# 10_Misc.net
KiCad netlist of a schematic drawn in Altium Designer
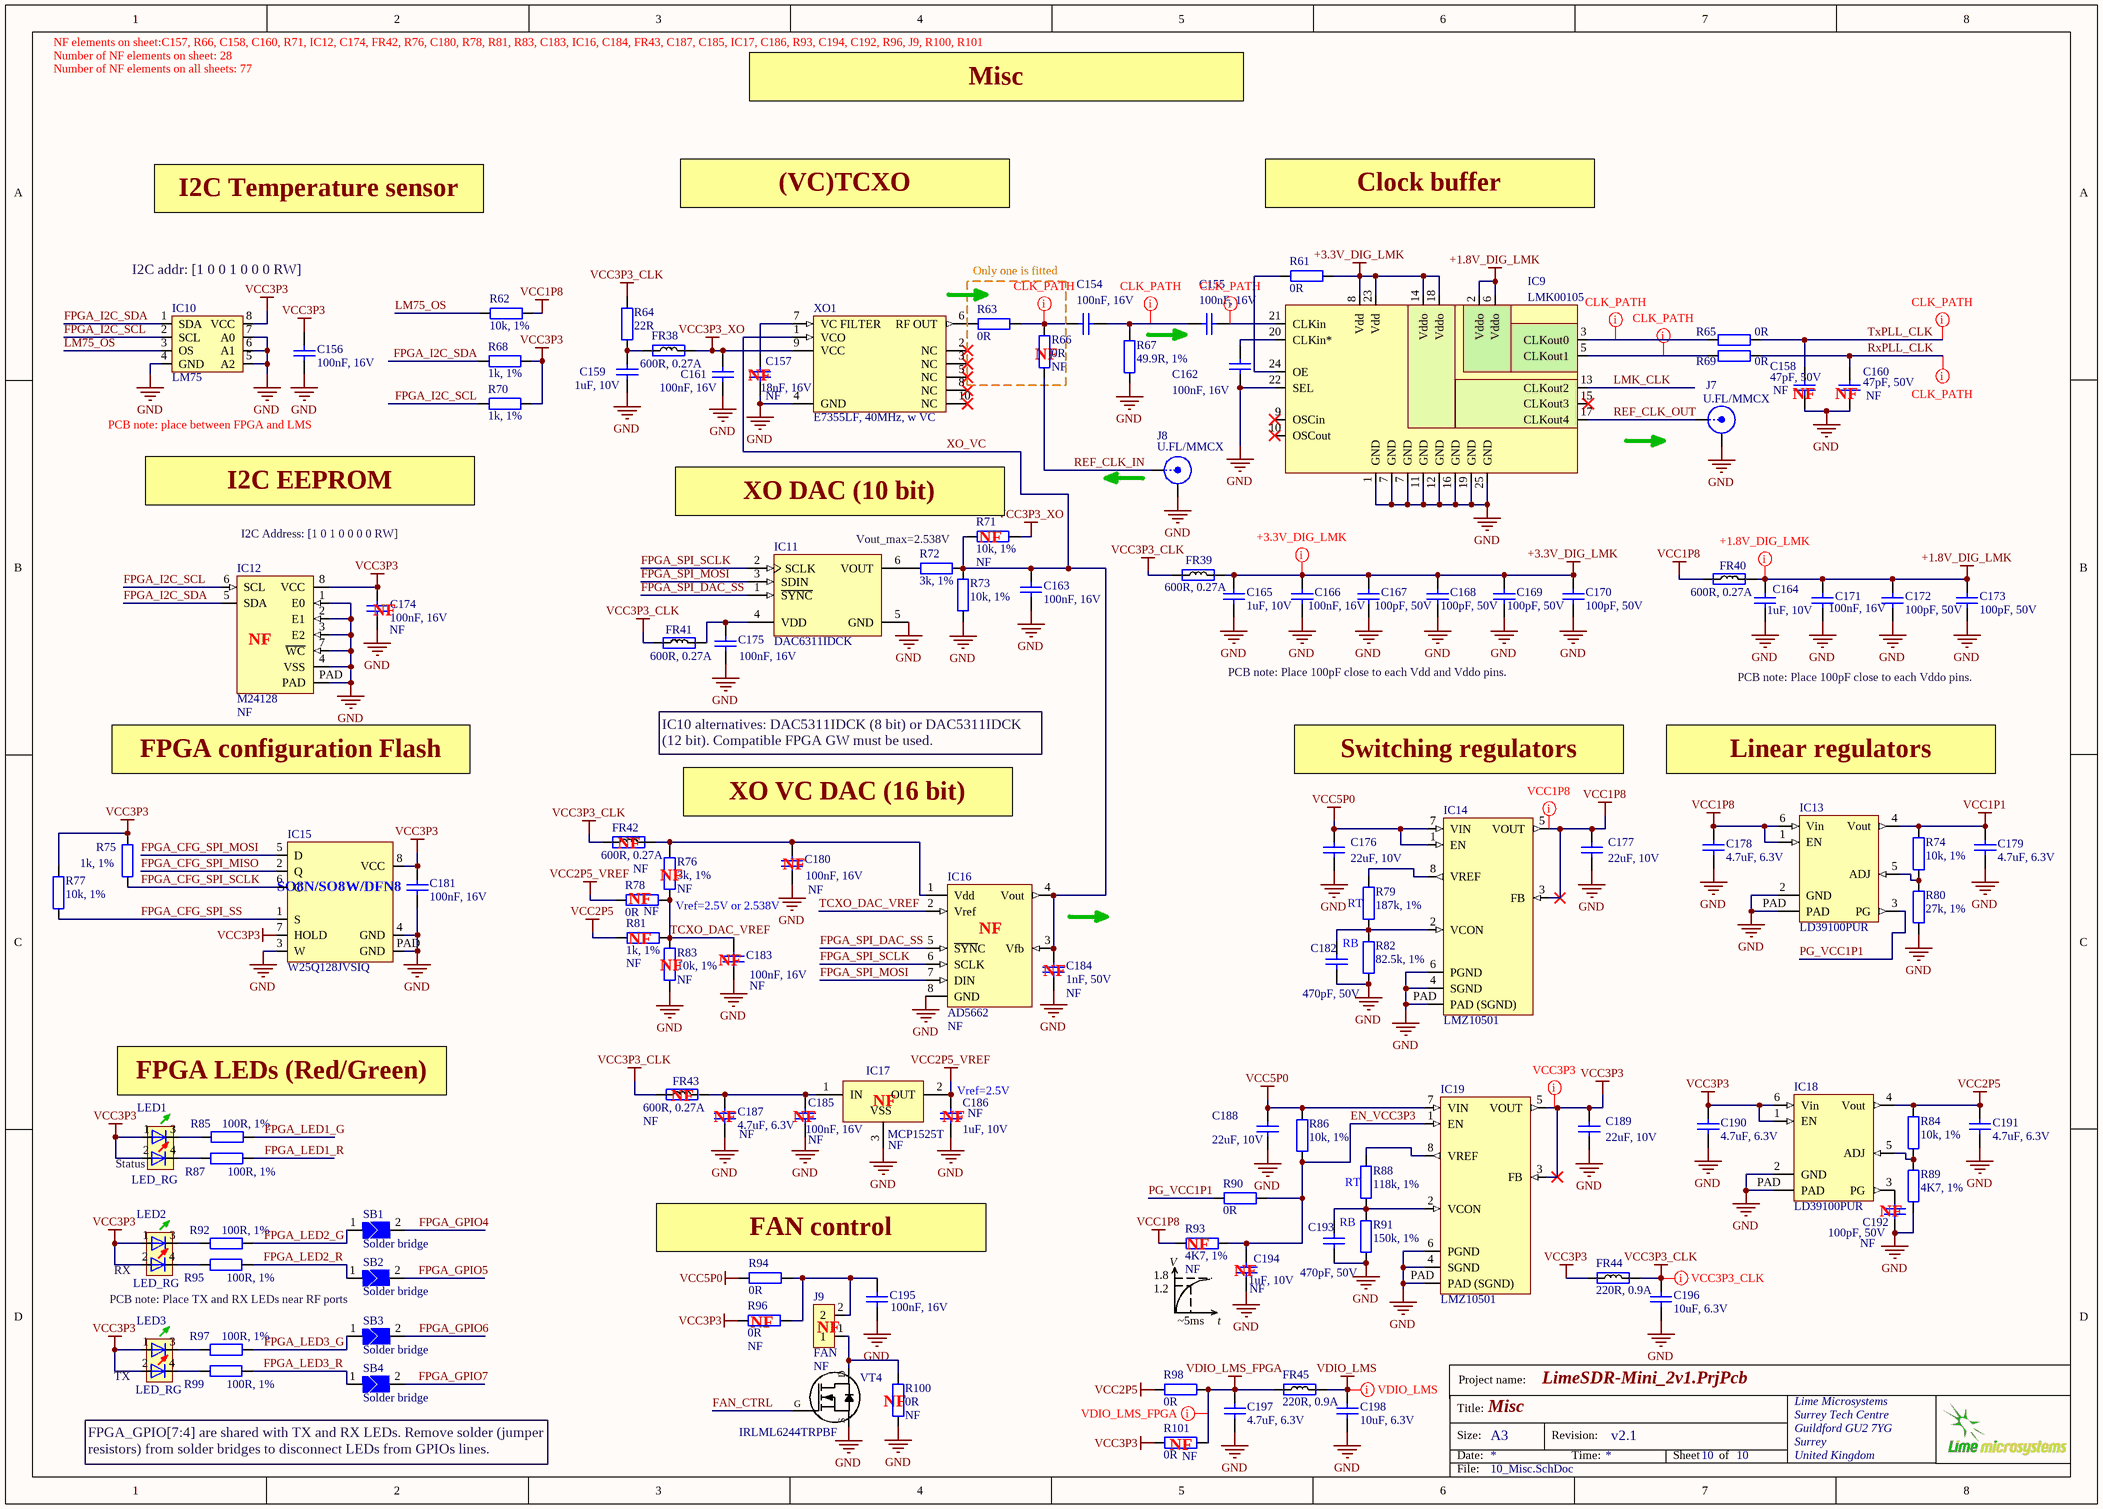
[diagram p0: 10_Misc.SchDoc]

(export (version "E")
  (design (tool "Eeschema 10.0.6"))
  (components
    (comp (ref "C154")
      (value "100nF, 16V")
      (footprint "CAP0402")
      (fields
        (field (name "MANUFACTURER") "Murata Electronics")
        (field (name "TOLERANCE") "10 %")
        (field (name "MANUFACTURER PART NUMBER") "GRM155R71C104KA88D")
      )
      (libsource (lib "LimeMicroAltiumLib_schLib") (part "Cap_0402"))
    )
    (comp (ref "C155")
      (value "100nF, 16V")
      (footprint "CAP0402")
      (fields
        (field (name "MANUFACTURER") "Murata Electronics")
        (field (name "TOLERANCE") "10 %")
        (field (name "MANUFACTURER PART NUMBER") "GRM155R71C104KA88D")
      )
      (libsource (lib "LimeMicroAltiumLib_schLib") (part "Cap_0402"))
    )
    (comp (ref "C156")
      (value "100nF, 16V")
      (footprint "CAP0402")
      (fields
        (field (name "TOLERANCE") "10 %")
        (field (name "MANUFACTURER") "Murata Electronics")
        (field (name "MANUFACTURER PART NUMBER") "GRM155R71C104KA88D")
      )
      (libsource (lib "") (part "Cap_0603_1"))
    )
    (comp (ref "C157")
      (value "18nF, 16V")
      (footprint "CAP0402")
      (fields
        (field (name "ASSEMBLY INFO") "NF")
        (field (name "MANUFACTURER") "Yageo")
        (field (name "TOLERANCE") "±10%")
      )
      (libsource (lib "LimeMicroAltiumLib_schLib") (part "Cap_0402"))
    )
    (comp (ref "C158")
      (value "47pF, 50V")
      (footprint "CAP0402")
      (fields
        (field (name "TOLERANCE") "±1%")
        (field (name "MANUFACTURER") "TDK Corporation")
        (field (name "ASSEMBLY INFO") "NF")
      )
      (libsource (lib "LimeMicroAltiumLib_schLib") (part "Cap_0402"))
    )
    (comp (ref "C159")
      (value "1uF, 10V")
      (footprint "CAP0402")
      (fields (field (name "MANUFACTURER") "TDK"))
      (libsource (lib "LimeMicroAltiumLib_schLib") (part "Cap_0402"))
    )
    (comp (ref "C160")
      (value "47pF, 50V")
      (footprint "CAP0402")
      (fields
        (field (name "TOLERANCE") "±1%")
        (field (name "MANUFACTURER") "TDK Corporation")
        (field (name "ASSEMBLY INFO") "NF")
      )
      (libsource (lib "LimeMicroAltiumLib_schLib") (part "Cap_0402"))
    )
    (comp (ref "C161")
      (value "100nF, 16V")
      (footprint "CAP0402")
      (fields
        (field (name "MANUFACTURER") "Murata Electronics")
        (field (name "TOLERANCE") "10 %")
        (field (name "MANUFACTURER PART NUMBER") "GRM155R71C104KA88D")
      )
      (libsource (lib "LimeMicroAltiumLib_schLib") (part "Cap_0402"))
    )
    (comp (ref "C162")
      (value "100nF, 16V")
      (footprint "CAP0402")
      (fields
        (field (name "MANUFACTURER") "Murata Electronics")
        (field (name "TOLERANCE") "10 %")
        (field (name "MANUFACTURER PART NUMBER") "GRM155R71C104KA88D")
      )
      (libsource (lib "LimeMicroAltiumLib_schLib") (part "Cap_0402"))
    )
    (comp (ref "C163")
      (value "100nF, 16V")
      (footprint "CAP0402")
      (fields
        (field (name "MANUFACTURER") "Murata Electronics")
        (field (name "TOLERANCE") "10 %")
        (field (name "MANUFACTURER PART NUMBER") "GRM155R71C104KA88D")
      )
      (libsource (lib "LimeMicroAltiumLib_schLib") (part "Cap_0402"))
    )
    (comp (ref "C164")
      (value "1uF, 10V")
      (footprint "CAP0402")
      (fields (field (name "MANUFACTURER") "TDK"))
      (libsource (lib "LimeMicroAltiumLib_schLib") (part "Cap_0402"))
    )
    (comp (ref "C165")
      (value "1uF, 10V")
      (footprint "CAP0402")
      (fields (field (name "MANUFACTURER") "TDK"))
      (libsource (lib "LimeMicroAltiumLib_schLib") (part "Cap_0402"))
    )
    (comp (ref "C166")
      (value "100nF, 16V")
      (footprint "CAP0402")
      (fields
        (field (name "MANUFACTURER") "Murata Electronics")
        (field (name "TOLERANCE") "10 %")
        (field (name "MANUFACTURER PART NUMBER") "GRM155R71C104KA88D")
      )
      (libsource (lib "LimeMicroAltiumLib_schLib") (part "Cap_0402"))
    )
    (comp (ref "C167")
      (value "100pF, 50V")
      (footprint "CAP0402")
      (fields (field (name "MANUFACTURER") "Yageo") (field (name "TOLERANCE") "±5%"))
      (libsource (lib "LimeMicroAltiumLib_schLib") (part "Cap_0402"))
    )
    (comp (ref "C168")
      (value "100pF, 50V")
      (footprint "CAP0402")
      (fields (field (name "MANUFACTURER") "Yageo") (field (name "TOLERANCE") "±5%"))
      (libsource (lib "LimeMicroAltiumLib_schLib") (part "Cap_0402"))
    )
    (comp (ref "C169")
      (value "100pF, 50V")
      (footprint "CAP0402")
      (fields (field (name "MANUFACTURER") "Yageo") (field (name "TOLERANCE") "±5%"))
      (libsource (lib "LimeMicroAltiumLib_schLib") (part "Cap_0402"))
    )
    (comp (ref "C170")
      (value "100pF, 50V")
      (footprint "CAP0402")
      (fields (field (name "MANUFACTURER") "Yageo") (field (name "TOLERANCE") "±5%"))
      (libsource (lib "LimeMicroAltiumLib_schLib") (part "Cap_0402"))
    )
    (comp (ref "C171")
      (value "100nF, 16V")
      (footprint "CAP0402")
      (fields
        (field (name "MANUFACTURER") "Murata Electronics")
        (field (name "TOLERANCE") "10 %")
        (field (name "MANUFACTURER PART NUMBER") "GRM155R71C104KA88D")
      )
      (libsource (lib "LimeMicroAltiumLib_schLib") (part "Cap_0402"))
    )
    (comp (ref "C172")
      (value "100pF, 50V")
      (footprint "CAP0402")
      (fields (field (name "MANUFACTURER") "Yageo") (field (name "TOLERANCE") "±5%"))
      (libsource (lib "LimeMicroAltiumLib_schLib") (part "Cap_0402"))
    )
    (comp (ref "C173")
      (value "100pF, 50V")
      (footprint "CAP0402")
      (fields (field (name "MANUFACTURER") "Yageo") (field (name "TOLERANCE") "±5%"))
      (libsource (lib "LimeMicroAltiumLib_schLib") (part "Cap_0402"))
    )
    (comp (ref "C174")
      (value "100nF, 16V")
      (footprint "CAP0402")
      (fields
        (field (name "TOLERANCE") "10 %")
        (field (name "MANUFACTURER") "Murata Electronics")
        (field (name "MANUFACTURER PART NUMBER") "GRM155R71C104KA88D")
        (field (name "ASSEMBLY INFO") "NF")
      )
      (libsource (lib "") (part "Cap_0603_1"))
    )
    (comp (ref "C175")
      (value "100nF, 16V")
      (footprint "CAP0402")
      (fields
        (field (name "TOLERANCE") "10 %")
        (field (name "MANUFACTURER") "Murata Electronics")
        (field (name "MANUFACTURER PART NUMBER") "GRM155R71C104KA88D")
      )
      (libsource (lib "") (part "Cap_0603_1"))
    )
    (comp (ref "C176")
      (value "22uF, 10V")
      (footprint "CAP0603")
      (fields (field (name "TOLERANCE") "20 %") (field (name "MANUFACTURER") "TDK Corporation"))
      (libsource (lib "") (part "Cap_0603_1"))
    )
    (comp (ref "C177")
      (value "22uF, 10V")
      (footprint "CAP0603")
      (fields (field (name "TOLERANCE") "20 %") (field (name "MANUFACTURER") "TDK Corporation"))
      (libsource (lib "") (part "Cap_0603_1"))
    )
    (comp (ref "C178")
      (value "4.7uF, 6.3V")
      (footprint "CAP0402")
      (fields
        (field (name "MANUFACTURER") "Murata Electronics North America")
        (field (name "TOLERANCE") "±20%")
      )
      (libsource (lib "LimeMicroAltiumLib_schLib") (part "Cap_0402"))
    )
    (comp (ref "C179")
      (value "4.7uF, 6.3V")
      (footprint "CAP0402")
      (fields
        (field (name "MANUFACTURER") "Murata Electronics North America")
        (field (name "TOLERANCE") "±20%")
      )
      (libsource (lib "LimeMicroAltiumLib_schLib") (part "Cap_0402"))
    )
    (comp (ref "C180")
      (value "100nF, 16V")
      (footprint "CAP0402")
      (fields
        (field (name "TOLERANCE") "10 %")
        (field (name "MANUFACTURER") "Murata Electronics")
        (field (name "MANUFACTURER PART NUMBER") "GRM155R71C104KA88D")
        (field (name "ASSEMBLY INFO") "NF")
      )
      (libsource (lib "") (part "Cap_0603_1"))
    )
    (comp (ref "C181")
      (value "100nF, 16V")
      (footprint "CAP0402")
      (fields
        (field (name "TOLERANCE") "10 %")
        (field (name "MANUFACTURER") "Murata Electronics")
        (field (name "MANUFACTURER PART NUMBER") "GRM155R71C104KA88D")
      )
      (libsource (lib "") (part "Cap_0603_1"))
    )
    (comp (ref "C182")
      (value "470pF, 50V")
      (footprint "CAP0402")
      (fields (field (name "TOLERANCE") "±5%") (field (name "MANUFACTURER") "TDK Corporation"))
      (libsource (lib "LimeMicroAltiumLib_schLib") (part "Cap_0402"))
    )
    (comp (ref "C183")
      (value "100nF, 16V")
      (footprint "CAP0402")
      (fields
        (field (name "TOLERANCE") "10 %")
        (field (name "MANUFACTURER") "Murata Electronics")
        (field (name "ASSEMBLY INFO") "NF")
      )
      (libsource (lib "LimeFPGAboard_schLib") (part "Cap_0603"))
    )
    (comp (ref "C184")
      (value "1nF, 50V")
      (footprint "CAP0402")
      (fields
        (field (name "ASSEMBLY INFO") "NF")
        (field (name "TOLERANCE") "10 %")
        (field (name "MANUFACTURER") "Murata Electronics")
      )
      (libsource (lib "") (part "Cap_0402_1"))
    )
    (comp (ref "C185")
      (value "100nF, 16V")
      (footprint "CAP0402")
      (fields
        (field (name "TOLERANCE") "10 %")
        (field (name "MANUFACTURER") "Murata Electronics")
        (field (name "ASSEMBLY INFO") "NF")
      )
      (libsource (lib "LimeFPGAboard_schLib") (part "Cap_0603"))
    )
    (comp (ref "C186")
      (value "1uF, 10V")
      (footprint "CAP0402")
      (fields (field (name "ASSEMBLY INFO") "NF") (field (name "MANUFACTURER") "TDK"))
      (libsource (lib "LimeMicroAltiumLib_schLib") (part "Cap_0402"))
    )
    (comp (ref "C187")
      (value "4.7uF, 6.3V")
      (footprint "CAP0402")
      (fields
        (field (name "ASSEMBLY INFO") "NF")
        (field (name "MANUFACTURER") "Murata Electronics North America")
        (field (name "TOLERANCE") "±20%")
      )
      (libsource (lib "LimeMicroAltiumLib_schLib") (part "Cap_0402"))
    )
    (comp (ref "C188")
      (value "22uF, 10V")
      (footprint "CAP0603")
      (fields (field (name "TOLERANCE") "20 %") (field (name "MANUFACTURER") "TDK Corporation"))
      (libsource (lib "") (part "Cap_0603_1"))
    )
    (comp (ref "C189")
      (value "22uF, 10V")
      (footprint "CAP0603")
      (fields (field (name "TOLERANCE") "20 %") (field (name "MANUFACTURER") "TDK Corporation"))
      (libsource (lib "") (part "Cap_0603_1"))
    )
    (comp (ref "C190")
      (value "4.7uF, 6.3V")
      (footprint "CAP0402")
      (fields
        (field (name "MANUFACTURER") "Murata Electronics North America")
        (field (name "TOLERANCE") "±20%")
      )
      (libsource (lib "LimeMicroAltiumLib_schLib") (part "Cap_0402"))
    )
    (comp (ref "C191")
      (value "4.7uF, 6.3V")
      (footprint "CAP0402")
      (fields
        (field (name "MANUFACTURER") "Murata Electronics North America")
        (field (name "TOLERANCE") "±20%")
      )
      (libsource (lib "LimeMicroAltiumLib_schLib") (part "Cap_0402"))
    )
    (comp (ref "C192")
      (value "100pF, 50V")
      (footprint "CAP0402")
      (fields
        (field (name "ASSEMBLY INFO") "NF")
        (field (name "MANUFACTURER") "Yageo")
        (field (name "TOLERANCE") "±5%")
      )
      (libsource (lib "LimeMicroAltiumLib_schLib") (part "Cap_0402"))
    )
    (comp (ref "C193")
      (value "470pF, 50V")
      (footprint "CAP0402")
      (fields (field (name "TOLERANCE") "±5%") (field (name "MANUFACTURER") "TDK Corporation"))
      (libsource (lib "LimeMicroAltiumLib_schLib") (part "Cap_0402"))
    )
    (comp (ref "C194")
      (value "1uF, 10V")
      (footprint "CAP0402")
      (fields (field (name "ASSEMBLY INFO") "NF") (field (name "MANUFACTURER") "TDK"))
      (libsource (lib "LimeMicroAltiumLib_schLib") (part "Cap_0402"))
    )
    (comp (ref "C195")
      (value "100nF, 16V")
      (footprint "CAP0402")
      (fields
        (field (name "TOLERANCE") "10 %")
        (field (name "MANUFACTURER") "Murata Electronics")
        (field (name "MANUFACTURER PART NUMBER") "GRM155R71C104KA88D")
      )
      (libsource (lib "") (part "Cap_0603_1"))
    )
    (comp (ref "C196")
      (value "10uF, 6.3V")
      (footprint "CAP0603")
      (fields (field (name "TOLERANCE") "±20%") (field (name "MANUFACTURER") "Yageo"))
      (libsource (lib "") (part "Cap_0603_1"))
    )
    (comp (ref "C197")
      (value "4.7uF, 6.3V")
      (footprint "CAP0402")
      (fields
        (field (name "MANUFACTURER") "Murata Electronics North America")
        (field (name "TOLERANCE") "±20%")
      )
      (libsource (lib "LimeMicroAltiumLib_schLib") (part "Cap_0402"))
    )
    (comp (ref "C198")
      (value "10uF, 6.3V")
      (footprint "CAP0603")
      (fields (field (name "TOLERANCE") "±20%") (field (name "MANUFACTURER") "Yageo"))
      (libsource (lib "") (part "Cap_0603_1"))
    )
    (comp (ref "FR38")
      (value "600R, 0.27A")
      (footprint "RES0201")
      (fields (field (name "MANUFACTURER") "Taiyo Yuden"))
      (libsource (lib "LimeMicroAltiumLib_schLib") (part "Ferrite"))
    )
    (comp (ref "FR39")
      (value "600R, 0.27A")
      (footprint "RES0201")
      (fields (field (name "MANUFACTURER") "Taiyo Yuden"))
      (libsource (lib "LimeMicroAltiumLib_schLib") (part "Ferrite"))
    )
    (comp (ref "FR40")
      (value "600R, 0.27A")
      (footprint "RES0201")
      (fields (field (name "MANUFACTURER") "Taiyo Yuden"))
      (libsource (lib "LimeMicroAltiumLib_schLib") (part "Ferrite"))
    )
    (comp (ref "FR41")
      (value "600R, 0.27A")
      (footprint "RES0201")
      (fields (field (name "MANUFACTURER") "Taiyo Yuden"))
      (libsource (lib "LimeMicroAltiumLib_schLib") (part "Ferrite"))
    )
    (comp (ref "FR42")
      (value "600R, 0.27A")
      (footprint "RES0201")
      (fields (field (name "MANUFACTURER") "Taiyo Yuden") (field (name "ASSEMBLY INFO") "NF"))
      (libsource (lib "LimeMicroAltiumLib_schLib") (part "Ferrite"))
    )
    (comp (ref "FR43")
      (value "600R, 0.27A")
      (footprint "RES0201")
      (fields (field (name "MANUFACTURER") "Taiyo Yuden") (field (name "ASSEMBLY INFO") "NF"))
      (libsource (lib "LimeMicroAltiumLib_schLib") (part "Ferrite"))
    )
    (comp (ref "FR44")
      (value "220R, 0.9A")
      (footprint "RES0402")
      (fields (field (name "MANUFACTURER") "TDK Corporation"))
      (libsource (lib "LimeFPGAboard_schLib") (part "Ferrite"))
    )
    (comp (ref "FR45")
      (value "220R, 0.9A")
      (footprint "RES0402")
      (fields (field (name "MANUFACTURER") "TDK Corporation"))
      (libsource (lib "LimeFPGAboard_schLib") (part "Ferrite"))
    )
    (comp (ref "IC9")
      (value "LMK00105")
      (footprint "LMK00105SQ")
      (fields (field (name "MANUFACTURER") "Texas Instruments"))
      (libsource (lib "LimeMicroAltiumLib_schLib") (part "LMK00105"))
    )
    (comp (ref "IC10")
      (value "LM75")
      (footprint "HWSON8_LM75")
      (fields (field (name "MANUFACTURER") "NXP Semiconductors"))
      (libsource (lib "LimeMicroAltiumLib_schLib") (part "LM75"))
    )
    (comp (ref "IC11")
      (value "DAC6311IDCK")
      (footprint "AD5601_SOT23-6")
      (fields (field (name "MANUFACTURER") "Texas Instruments"))
      (libsource (lib "LimeMicroAltiumLib_schLib") (part "AD5601BKSZ-REEL7"))
    )
    (comp (ref "IC12")
      (value "M24128")
      (footprint "M24128-DFMC6TG")
      (fields (field (name "MANUFACTURER") "STMicroelectronics") (field (name "ASSEMBLY INFO") "NF"))
      (libsource (lib "LimeMicroAltiumLib_schLib") (part "M24128-DFMC6TG"))
    )
    (comp (ref "IC13")
      (value "LD39100PUR")
      (footprint "LD39100PUR")
      (fields (field (name "MANUFACTURER") "STMicroelectronics"))
      (libsource (lib "LimeMicroAltiumLib_schLib") (part "LD39100PUR"))
    )
    (comp (ref "IC14")
      (value "LMZ10501")
      (footprint "LMZ10501")
      (fields (field (name "MANUFACTURER") "Texas Instruments"))
      (libsource (lib "LimeMicroAltiumLib_schLib") (part "LMZ10501"))
    )
    (comp (ref "IC15")
      (value "W25Q128JVSIQ")
      (footprint "S25FL164K_WSON8_DFN6")
      (fields (field (name "MANUFACTURER") "Winbond"))
      (libsource (lib "LimeMicroAltiumLib_schLib_r03") (part "M25P40_with_pad"))
    )
    (comp (ref "IC16")
      (value "AD5662")
      (footprint "AD5662_SOT23-8")
      (fields (field (name "MANUFACTURER") "Analog Devices Inc.") (field (name "ASSEMBLY INFO") "NF"))
      (libsource (lib "LimeMicroAltiumLib_schLib") (part "AD5662"))
    )
    (comp (ref "IC17")
      (value "MCP1525T")
      (footprint "SOT23-3_v2")
      (description "2.5V Voltage Reference, 3-Pin SOT-23, Industrial Temperature, Tape and Reel")
      (fields
        (field (name "MANUFACTURER") "Microchip Technology")
        (field (name "TOLERANCE") "±1%")
        (field (name "ASSEMBLY INFO") "NF")
      )
      (libsource (lib "LimeMicroAltiumLib_schLib") (part "MCP1525T-I/TT"))
    )
    (comp (ref "IC18")
      (value "LD39100PUR")
      (footprint "LD39100PUR")
      (fields (field (name "MANUFACTURER") "STMicroelectronics"))
      (libsource (lib "LimeMicroAltiumLib_schLib") (part "LD39100PUR"))
    )
    (comp (ref "IC19")
      (value "LMZ10501")
      (footprint "LMZ10501")
      (fields (field (name "MANUFACTURER") "Texas Instruments"))
      (libsource (lib "LimeMicroAltiumLib_schLib") (part "LMZ10501"))
    )
    (comp (ref "J7")
      (value "U.FL/MMCX")
      (footprint "MMCX_UFL_conn_u")
      (description "CONN UMC RCPT STR 50 OHM SMD")
      (fields (field (name "MANUFACTURER") "Molex, LLC"))
      (libsource (lib "LimeMicroAltiumLib_schLib") (part "RF_IF_connector"))
    )
    (comp (ref "J8")
      (value "U.FL/MMCX")
      (footprint "MMCX_UFL_conn_u")
      (description "CONN UMC RCPT STR 50 OHM SMD")
      (fields (field (name "MANUFACTURER") "Molex, LLC"))
      (libsource (lib "LimeMicroAltiumLib_schLib") (part "RF_IF_connector"))
    )
    (comp (ref "J9")
      (value "FAN")
      (footprint "Header2x1_TH_v2")
      (fields (field (name "ASSEMBLY INFO") "NF") (field (name "MANUFACTURER") "3M"))
      (libsource (lib "LimeFPGAboard_schLib") (part "Jumper"))
    )
    (comp (ref "LED1")
      (value "LED_RG")
      (footprint "LED-2x0603")
      (fields (field (name "MANUFACTURER") "Avago Technologies US Inc."))
      (libsource (lib "LimeMicroAltiumLib_schLib") (part "LED_green_red_SMD"))
    )
    (comp (ref "LED2")
      (value "LED_RG")
      (footprint "LED-2x0603")
      (fields (field (name "MANUFACTURER") "Avago Technologies US Inc."))
      (libsource (lib "LimeMicroAltiumLib_schLib") (part "LED_green_red_SMD"))
    )
    (comp (ref "LED3")
      (value "LED_RG")
      (footprint "LED-2x0603")
      (fields (field (name "MANUFACTURER") "Avago Technologies US Inc."))
      (libsource (lib "LimeMicroAltiumLib_schLib") (part "LED_green_red_SMD"))
    )
    (comp (ref "R61")
      (value "0R")
      (footprint "RES0402")
      (fields (field (name "MANUFACTURER") "Yageo") (field (name "TOLERANCE") "Jumper"))
      (libsource (lib "LimeMicroAltiumLib_schLib") (part "Res_0402"))
    )
    (comp (ref "R62")
      (value "10k, 1%")
      (footprint "RES0402")
      (fields (field (name "MANUFACTURER") "Yageo") (field (name "TOLERANCE") "±1%"))
      (libsource (lib "LimeMicroAltiumLib_schLib") (part "Res_0402"))
    )
    (comp (ref "R63")
      (value "0R")
      (footprint "RES0402")
      (fields (field (name "MANUFACTURER") "Yageo") (field (name "TOLERANCE") "Jumper"))
      (libsource (lib "LimeMicroAltiumLib_schLib") (part "Res_0402"))
    )
    (comp (ref "R64")
      (value "22R")
      (footprint "RES0402")
      (fields (field (name "TOLERANCE") "±1%") (field (name "MANUFACTURER") "Yageo"))
      (libsource (lib "LimeFPGAboard_schLib") (part "Res_0402"))
    )
    (comp (ref "R65")
      (value "0R")
      (footprint "RES0402")
      (fields (field (name "MANUFACTURER") "Yageo") (field (name "TOLERANCE") "Jumper"))
      (libsource (lib "LimeFPGAboard_schLib") (part "Res_0402"))
    )
    (comp (ref "R66")
      (value "0R")
      (footprint "RES0402")
      (fields
        (field (name "ASSEMBLY INFO") "NF")
        (field (name "MANUFACTURER") "Yageo")
        (field (name "TOLERANCE") "Jumper")
      )
      (libsource (lib "LimeMicroAltiumLib_schLib") (part "Res_0402"))
    )
    (comp (ref "R67")
      (value "49.9R, 1%")
      (footprint "RES0402")
      (fields
        (field (name "TOLERANCE") "±1%")
        (field (name "MANUFACTURER") "Samsung Electro-Mechanics America, Inc.")
      )
      (libsource (lib "LimeMicroAltiumLib_schLib") (part "Res_0402"))
    )
    (comp (ref "R68")
      (value "1k, 1%")
      (footprint "RES0402")
      (fields (field (name "MANUFACTURER") "Stackpole Electronics Inc") (field (name "TOLERANCE") "±1%"))
      (libsource (lib "LimeMicroAltiumLib_schLib") (part "Res_0402"))
    )
    (comp (ref "R69")
      (value "0R")
      (footprint "RES0402")
      (fields (field (name "MANUFACTURER") "Yageo") (field (name "TOLERANCE") "Jumper"))
      (libsource (lib "LimeFPGAboard_schLib") (part "Res_0402"))
    )
    (comp (ref "R70")
      (value "1k, 1%")
      (footprint "RES0402")
      (fields (field (name "MANUFACTURER") "Stackpole Electronics Inc") (field (name "TOLERANCE") "±1%"))
      (libsource (lib "LimeMicroAltiumLib_schLib") (part "Res_0402"))
    )
    (comp (ref "R71")
      (value "10k, 1%")
      (footprint "RES0402")
      (fields
        (field (name "ASSEMBLY INFO") "NF")
        (field (name "MANUFACTURER") "Yageo")
        (field (name "TOLERANCE") "±1%")
      )
      (libsource (lib "LimeMicroAltiumLib_schLib") (part "Res_0402"))
    )
    (comp (ref "R72")
      (value "3k, 1%")
      (footprint "RES0402")
      (fields (field (name "TOLERANCE") "±1%") (field (name "MANUFACTURER") "Vishay Dale"))
      (libsource (lib "LimeMicroAltiumLib_schLib") (part "Res_0402"))
    )
    (comp (ref "R73")
      (value "10k, 1%")
      (footprint "RES0402")
      (fields (field (name "MANUFACTURER") "Yageo") (field (name "TOLERANCE") "±1%"))
      (libsource (lib "LimeMicroAltiumLib_schLib") (part "Res_0402"))
    )
    (comp (ref "R74")
      (value "10k, 1%")
      (footprint "RES0402")
      (fields (field (name "MANUFACTURER") "Yageo") (field (name "TOLERANCE") "±1%"))
      (libsource (lib "LimeMicroAltiumLib_schLib") (part "Res_0402"))
    )
    (comp (ref "R75")
      (value "1k, 1%")
      (footprint "RES0402")
      (fields (field (name "MANUFACTURER") "Stackpole Electronics Inc") (field (name "TOLERANCE") "±1%"))
      (libsource (lib "LimeMicroAltiumLib_schLib") (part "Res_0402"))
    )
    (comp (ref "R76")
      (value "3k, 1%")
      (footprint "RES0402")
      (fields
        (field (name "ASSEMBLY INFO") "NF")
        (field (name "TOLERANCE") "±1%")
        (field (name "MANUFACTURER") "Vishay Dale")
      )
      (libsource (lib "") (part "Res_0402_1"))
    )
    (comp (ref "R77")
      (value "10k, 1%")
      (footprint "RES0402")
      (fields (field (name "MANUFACTURER") "Yageo") (field (name "TOLERANCE") "±1%"))
      (libsource (lib "LimeMicroAltiumLib_schLib") (part "Res_0402"))
    )
    (comp (ref "R78")
      (value "0R")
      (footprint "RES0402")
      (fields
        (field (name "ASSEMBLY INFO") "NF")
        (field (name "MANUFACTURER") "Yageo")
        (field (name "TOLERANCE") "Jumper")
      )
      (libsource (lib "LimeMicroAltiumLib_schLib") (part "Res_0402"))
    )
    (comp (ref "R79")
      (value "187k, 1%")
      (footprint "RES0402")
      (fields (field (name "TOLERANCE") "±1%") (field (name "MANUFACTURER") "Yageo"))
      (libsource (lib "LimeMicroAltiumLib_schLib") (part "Res_0402"))
    )
    (comp (ref "R80")
      (value "27k, 1%")
      (footprint "RES0402")
      (fields (field (name "MANUFACTURER") "Yageo") (field (name "TOLERANCE") "1%"))
      (libsource (lib "LimeFPGAboard_schLib") (part "Res_0402"))
    )
    (comp (ref "R81")
      (value "1k, 1%")
      (footprint "RES0402")
      (fields
        (field (name "ASSEMBLY INFO") "NF")
        (field (name "MANUFACTURER") "Stackpole Electronics Inc")
        (field (name "TOLERANCE") "±1%")
      )
      (libsource (lib "") (part "Res_0402_1"))
    )
    (comp (ref "R82")
      (value "82.5k, 1%")
      (footprint "RES0402")
      (fields (field (name "TOLERANCE") "±1%") (field (name "MANUFACTURER") "Yageo"))
      (libsource (lib "LimeMicroAltiumLib_schLib") (part "Res_0402"))
    )
    (comp (ref "R83")
      (value "10k, 1%")
      (footprint "RES0402")
      (fields
        (field (name "ASSEMBLY INFO") "NF")
        (field (name "MANUFACTURER") "Yageo")
        (field (name "TOLERANCE") "±1%")
      )
      (libsource (lib "") (part "Res_0402_1"))
    )
    (comp (ref "R84")
      (value "10k, 1%")
      (footprint "RES0402")
      (fields (field (name "MANUFACTURER") "Yageo") (field (name "TOLERANCE") "±1%"))
      (libsource (lib "LimeMicroAltiumLib_schLib") (part "Res_0402"))
    )
    (comp (ref "R85")
      (value "100R, 1%")
      (footprint "RES0402")
      (fields (field (name "TOLERANCE") "±1%") (field (name "MANUFACTURER") "Stackpole Electronics Inc."))
      (libsource (lib "LimeMicroAltiumLib_schLib") (part "Res_0402"))
    )
    (comp (ref "R86")
      (value "10k, 1%")
      (footprint "RES0402")
      (fields (field (name "MANUFACTURER") "Yageo") (field (name "TOLERANCE") "±1%"))
      (libsource (lib "LimeMicroAltiumLib_schLib") (part "Res_0402"))
    )
    (comp (ref "R87")
      (value "100R, 1%")
      (footprint "RES0402")
      (fields (field (name "TOLERANCE") "±1%") (field (name "MANUFACTURER") "Stackpole Electronics Inc."))
      (libsource (lib "LimeMicroAltiumLib_schLib") (part "Res_0402"))
    )
    (comp (ref "R88")
      (value "118k, 1%")
      (footprint "RES0402")
      (fields (field (name "MANUFACTURER") "Yageo") (field (name "TOLERANCE") "±1%"))
      (libsource (lib "LimeMicroAltiumLib_schLib") (part "Res_0402"))
    )
    (comp (ref "R89")
      (value "4K7, 1%")
      (footprint "RES0402")
      (fields (field (name "MANUFACTURER") "Yageo") (field (name "TOLERANCE") "±1%"))
      (libsource (lib "LimeFPGAboard_schLib") (part "Res_0402"))
    )
    (comp (ref "R90")
      (value "0R")
      (footprint "RES0402")
      (fields (field (name "MANUFACTURER") "Yageo") (field (name "TOLERANCE") "Jumper"))
      (libsource (lib "LimeMicroAltiumLib_schLib") (part "Res_0402"))
    )
    (comp (ref "R91")
      (value "150k, 1%")
      (footprint "RES0402")
      (fields (field (name "TOLERANCE") "1%"))
      (libsource (lib "LimeMicroAltiumLib_schLib") (part "Res_0402"))
    )
    (comp (ref "R92")
      (value "100R, 1%")
      (footprint "RES0402")
      (fields (field (name "TOLERANCE") "±1%") (field (name "MANUFACTURER") "Stackpole Electronics Inc."))
      (libsource (lib "LimeMicroAltiumLib_schLib") (part "Res_0402"))
    )
    (comp (ref "R93")
      (value "4K7, 1%")
      (footprint "RES0402")
      (fields
        (field (name "MANUFACTURER") "Yageo")
        (field (name "TOLERANCE") "±1%")
        (field (name "ASSEMBLY INFO") "NF")
      )
      (libsource (lib "LimeFPGAboard_schLib") (part "Res_0402"))
    )
    (comp (ref "R94")
      (value "0R")
      (footprint "RES0402")
      (fields (field (name "MANUFACTURER") "Yageo") (field (name "TOLERANCE") "Jumper"))
      (libsource (lib "LimeMicroAltiumLib_schLib") (part "Res_0402"))
    )
    (comp (ref "R95")
      (value "100R, 1%")
      (footprint "RES0402")
      (fields (field (name "TOLERANCE") "±1%") (field (name "MANUFACTURER") "Stackpole Electronics Inc."))
      (libsource (lib "LimeMicroAltiumLib_schLib") (part "Res_0402"))
    )
    (comp (ref "R96")
      (value "0R")
      (footprint "RES0402")
      (fields
        (field (name "ASSEMBLY INFO") "NF")
        (field (name "MANUFACTURER") "Yageo")
        (field (name "TOLERANCE") "Jumper")
      )
      (libsource (lib "LimeMicroAltiumLib_schLib") (part "Res_0402"))
    )
    (comp (ref "R97")
      (value "100R, 1%")
      (footprint "RES0402")
      (fields (field (name "TOLERANCE") "±1%") (field (name "MANUFACTURER") "Stackpole Electronics Inc."))
      (libsource (lib "LimeMicroAltiumLib_schLib") (part "Res_0402"))
    )
    (comp (ref "R98")
      (value "0R")
      (footprint "RES0402")
      (fields (field (name "MANUFACTURER") "Yageo") (field (name "TOLERANCE") "Jumper"))
      (libsource (lib "LimeFPGAboard_schLib") (part "Res_0402"))
    )
    (comp (ref "R99")
      (value "100R, 1%")
      (footprint "RES0402")
      (fields (field (name "TOLERANCE") "±1%") (field (name "MANUFACTURER") "Stackpole Electronics Inc."))
      (libsource (lib "LimeMicroAltiumLib_schLib") (part "Res_0402"))
    )
    (comp (ref "R100")
      (value "0R")
      (footprint "RES0402")
      (fields
        (field (name "ASSEMBLY INFO") "NF")
        (field (name "MANUFACTURER") "Yageo")
        (field (name "TOLERANCE") "Jumper")
      )
      (libsource (lib "LimeMicroAltiumLib_schLib") (part "Res_0402"))
    )
    (comp (ref "R101")
      (value "0R")
      (footprint "RES0402")
      (fields
        (field (name "MANUFACTURER") "Yageo")
        (field (name "ASSEMBLY INFO") "NF")
        (field (name "TOLERANCE") "Jumper")
      )
      (libsource (lib "LimeFPGAboard_schLib") (part "Res_0402"))
    )
    (comp (ref "SB1")
      (value "Solder bridge")
      (footprint "SOLDER_BRIDGE_TRIANGULAR_v2")
      (description "Can be shorted out using solder paste or 0402-1206 resistor")
      (fields (field (name "MANUFACTURER") "Yageo") (field (name "TOLERANCE") "Jumper"))
      (libsource (lib "LimeMicroAltiumLib_schLib_r03") (part "SOLDER_BRIDGE_TRIANGULAR"))
    )
    (comp (ref "SB2")
      (value "Solder bridge")
      (footprint "SOLDER_BRIDGE_TRIANGULAR_v2")
      (description "Can be shorted out using solder paste or 0402-1206 resistor")
      (fields (field (name "MANUFACTURER") "Yageo") (field (name "TOLERANCE") "Jumper"))
      (libsource (lib "LimeMicroAltiumLib_schLib_r03") (part "SOLDER_BRIDGE_TRIANGULAR"))
    )
    (comp (ref "SB3")
      (value "Solder bridge")
      (footprint "SOLDER_BRIDGE_TRIANGULAR_v2")
      (description "Can be shorted out using solder paste or 0402-1206 resistor")
      (fields (field (name "MANUFACTURER") "Yageo") (field (name "TOLERANCE") "Jumper"))
      (libsource (lib "LimeMicroAltiumLib_schLib_r03") (part "SOLDER_BRIDGE_TRIANGULAR"))
    )
    (comp (ref "SB4")
      (value "Solder bridge")
      (footprint "SOLDER_BRIDGE_TRIANGULAR_v2")
      (description "Can be shorted out using solder paste or 0402-1206 resistor")
      (fields (field (name "MANUFACTURER") "Yageo") (field (name "TOLERANCE") "Jumper"))
      (libsource (lib "LimeMicroAltiumLib_schLib_r03") (part "SOLDER_BRIDGE_TRIANGULAR"))
    )
    (comp (ref "VT4")
      (value "IRLML6244TRPBF")
      (footprint "SOT23-3")
      (description "NDS331N")
      (fields (field (name "MANUFACTURER") "Infineon Technologies"))
      (libsource (lib "LimeFPGAboard_schLib") (part "NDS331N"))
    )
    (comp (ref "XO1")
      (value "E7355LF, 40MHz, w VC")
      (footprint "RAKON_RTX5032A")
      (fields (field (name "MANUFACTURER") "Rakon"))
      (libsource (lib "LimeMicroAltiumLib_schLib") (part "Rakon_RTX5032A"))
    )
  )
  (nets
    (net (code "1") (name "+1.8V_DIG_LMK") (class "Default")
      (node (ref "C164") (pin "2") (pinfunction "2_2") (pintype "passive"))
      (node (ref "C171") (pin "2") (pinfunction "2_2") (pintype "passive"))
      (node (ref "C172") (pin "2") (pinfunction "2_2") (pintype "passive"))
      (node (ref "C173") (pin "2") (pinfunction "2_2") (pintype "passive"))
      (node (ref "FR40") (pin "2") (pinfunction "2_2") (pintype "passive"))
      (node (ref "IC9") (pin "2") (pinfunction "Vddo_2") (pintype "passive"))
      (node (ref "IC9") (pin "6") (pinfunction "Vddo_6") (pintype "passive"))
    )
    (net (code "2") (name "+3.3V_DIG_LMK") (class "Default")
      (node (ref "C165") (pin "2") (pinfunction "2_2") (pintype "passive"))
      (node (ref "C166") (pin "2") (pinfunction "2_2") (pintype "passive"))
      (node (ref "C167") (pin "2") (pinfunction "2_2") (pintype "passive"))
      (node (ref "C168") (pin "2") (pinfunction "2_2") (pintype "passive"))
      (node (ref "C169") (pin "2") (pinfunction "2_2") (pintype "passive"))
      (node (ref "C170") (pin "2") (pinfunction "2_2") (pintype "passive"))
      (node (ref "FR39") (pin "2") (pinfunction "2_2") (pintype "passive"))
      (node (ref "IC9") (pin "14") (pinfunction "Vddo_14") (pintype "passive"))
      (node (ref "IC9") (pin "18") (pinfunction "Vddo_18") (pintype "passive"))
      (node (ref "IC9") (pin "23") (pinfunction "Vdd_23") (pintype "passive"))
      (node (ref "IC9") (pin "8") (pinfunction "Vdd_8") (pintype "passive"))
      (node (ref "R61") (pin "2") (pinfunction "2_2") (pintype "passive"))
    )
    (net (code "3") (name "/EN_VCC3P3") (class "Default")
      (node (ref "C194") (pin "2") (pinfunction "2_2") (pintype "passive"))
      (node (ref "IC19") (pin "1") (pinfunction "EN_1") (pintype "input"))
      (node (ref "R86") (pin "1") (pinfunction "1_1") (pintype "passive"))
      (node (ref "R90") (pin "2") (pinfunction "2_2") (pintype "passive"))
      (node (ref "R93") (pin "1") (pinfunction "1_1") (pintype "passive"))
    )
    (net (code "4") (name "/FAN_CTRL") (class "Default")
      (node (ref "VT4") (pin "G") (pinfunction "G_G") (pintype "passive"))
    )
    (net (code "5") (name "/FPGA_CFG_SPI_MISO") (class "Default")
      (node (ref "IC15") (pin "2") (pinfunction "Q_2") (pintype "passive"))
    )
    (net (code "6") (name "/FPGA_CFG_SPI_MOSI") (class "Default")
      (node (ref "IC15") (pin "5") (pinfunction "D_5") (pintype "passive"))
    )
    (net (code "7") (name "/FPGA_CFG_SPI_SCLK") (class "Default")
      (node (ref "IC15") (pin "6") (pinfunction "C_6") (pintype "passive"))
      (node (ref "R75") (pin "1") (pinfunction "1_1") (pintype "passive"))
    )
    (net (code "8") (name "/FPGA_CFG_SPI_SS") (class "Default")
      (node (ref "IC15") (pin "1") (pinfunction "S_1") (pintype "passive"))
      (node (ref "R77") (pin "1") (pinfunction "1_1") (pintype "passive"))
    )
    (net (code "9") (name "/FPGA_GPIO4") (class "Default")
      (node (ref "SB1") (pin "2") (pinfunction "2_2") (pintype "passive"))
    )
    (net (code "10") (name "/FPGA_GPIO5") (class "Default")
      (node (ref "SB2") (pin "2") (pinfunction "2_2") (pintype "passive"))
    )
    (net (code "11") (name "/FPGA_GPIO6") (class "Default")
      (node (ref "SB3") (pin "2") (pinfunction "2_2") (pintype "passive"))
    )
    (net (code "12") (name "/FPGA_GPIO7") (class "Default")
      (node (ref "SB4") (pin "2") (pinfunction "2_2") (pintype "passive"))
    )
    (net (code "13") (name "/FPGA_I2C_SCL") (class "Default")
      (node (ref "IC10") (pin "2") (pinfunction "SCL_2") (pintype "passive"))
      (node (ref "IC12") (pin "6") (pinfunction "SCL_6") (pintype "input"))
      (node (ref "R70") (pin "2") (pinfunction "2_2") (pintype "passive"))
    )
    (net (code "14") (name "/FPGA_I2C_SDA") (class "Default")
      (node (ref "IC10") (pin "1") (pinfunction "SDA_1") (pintype "passive"))
      (node (ref "IC12") (pin "5") (pinfunction "SDA_5") (pintype "bidirectional"))
      (node (ref "R68") (pin "2") (pinfunction "2_2") (pintype "passive"))
    )
    (net (code "15") (name "/FPGA_LED1_G") (class "Default")
      (node (ref "R85") (pin "2") (pinfunction "2_2") (pintype "passive"))
    )
    (net (code "16") (name "/FPGA_LED1_R") (class "Default")
      (node (ref "R87") (pin "2") (pinfunction "2_2") (pintype "passive"))
    )
    (net (code "17") (name "/FPGA_LED2_G") (class "Default")
      (node (ref "R92") (pin "2") (pinfunction "2_2") (pintype "passive"))
      (node (ref "SB1") (pin "1") (pinfunction "1_1") (pintype "passive"))
    )
    (net (code "18") (name "/FPGA_LED2_R") (class "Default")
      (node (ref "R95") (pin "2") (pinfunction "2_2") (pintype "passive"))
      (node (ref "SB2") (pin "1") (pinfunction "1_1") (pintype "passive"))
    )
    (net (code "19") (name "/FPGA_LED3_G") (class "Default")
      (node (ref "R97") (pin "2") (pinfunction "2_2") (pintype "passive"))
      (node (ref "SB3") (pin "1") (pinfunction "1_1") (pintype "passive"))
    )
    (net (code "20") (name "/FPGA_LED3_R") (class "Default")
      (node (ref "R99") (pin "2") (pinfunction "2_2") (pintype "passive"))
      (node (ref "SB4") (pin "1") (pinfunction "1_1") (pintype "passive"))
    )
    (net (code "21") (name "/FPGA_SPI_DAC_SS") (class "Default")
      (node (ref "IC11") (pin "1") (pinfunction "~{SYNC}_1") (pintype "input"))
      (node (ref "IC16") (pin "5") (pinfunction "~{SYN}C_5") (pintype "input"))
    )
    (net (code "22") (name "/FPGA_SPI_MOSI") (class "Default")
      (node (ref "IC11") (pin "3") (pinfunction "SDIN_3") (pintype "input"))
      (node (ref "IC16") (pin "7") (pinfunction "DIN_7") (pintype "input"))
    )
    (net (code "23") (name "/FPGA_SPI_SCLK") (class "Default")
      (node (ref "IC11") (pin "2") (pinfunction "SCLK_2") (pintype "input"))
      (node (ref "IC16") (pin "6") (pinfunction "SCLK_6") (pintype "input"))
    )
    (net (code "24") (name "/LM75_OS") (class "Default")
      (node (ref "IC10") (pin "3") (pinfunction "OS_3") (pintype "passive"))
      (node (ref "R62") (pin "1") (pinfunction "1_1") (pintype "passive"))
    )
    (net (code "25") (name "/LMK_CLK") (class "Default")
      (node (ref "IC9") (pin "13") (pinfunction "CLKout2_13") (pintype "passive"))
    )
    (net (code "26") (name "/PG_VCC1P1") (class "Default")
      (node (ref "IC13") (pin "3") (pinfunction "PG_3") (pintype "output"))
      (node (ref "R90") (pin "1") (pinfunction "1_1") (pintype "passive"))
    )
    (net (code "27") (name "/REF_CLK_IN") (class "Default")
      (node (ref "J8") (pin "1") (pinfunction "X_1") (pintype "passive"))
      (node (ref "R66") (pin "1") (pinfunction "1_1") (pintype "passive"))
    )
    (net (code "28") (name "/REF_CLK_OUT") (class "Default")
      (node (ref "IC9") (pin "17") (pinfunction "CLKout4_17") (pintype "passive"))
      (node (ref "J7") (pin "1") (pinfunction "X_1") (pintype "passive"))
    )
    (net (code "29") (name "/RxPLL_CLK") (class "Default")
      (node (ref "C160") (pin "2") (pinfunction "2_2") (pintype "passive"))
      (node (ref "R69") (pin "1") (pinfunction "1_1") (pintype "passive"))
    )
    (net (code "30") (name "/TCXO_DAC_VREF") (class "Default")
      (node (ref "C183") (pin "1") (pinfunction "1_1") (pintype "passive"))
      (node (ref "IC16") (pin "2") (pinfunction "Vref_2") (pintype "input"))
      (node (ref "R76") (pin "1") (pinfunction "1_1") (pintype "passive"))
      (node (ref "R78") (pin "2") (pinfunction "2_2") (pintype "passive"))
      (node (ref "R81") (pin "1") (pinfunction "1_1") (pintype "passive"))
      (node (ref "R83") (pin "1") (pinfunction "1_1") (pintype "passive"))
    )
    (net (code "31") (name "/TxPLL_CLK") (class "Default")
      (node (ref "C158") (pin "2") (pinfunction "2_2") (pintype "passive"))
      (node (ref "R65") (pin "1") (pinfunction "1_1") (pintype "passive"))
    )
    (net (code "32") (name "/XO_VC") (class "Default")
      (node (ref "C163") (pin "2") (pinfunction "2_2") (pintype "passive"))
      (node (ref "C184") (pin "1") (pinfunction "1_1") (pintype "passive"))
      (node (ref "IC16") (pin "3") (pinfunction "Vfb_3") (pintype "input"))
      (node (ref "IC16") (pin "4") (pinfunction "Vout_4") (pintype "output"))
      (node (ref "R71") (pin "1") (pinfunction "1_1") (pintype "passive"))
      (node (ref "R72") (pin "1") (pinfunction "1_1") (pintype "passive"))
      (node (ref "R73") (pin "1") (pinfunction "1_1") (pintype "passive"))
      (node (ref "XO1") (pin "1") (pinfunction "VCO_1") (pintype "input"))
    )
    (net (code "33") (name "GND") (class "Default")
      (node (ref "C156") (pin "2") (pinfunction "2_2") (pintype "passive"))
      (node (ref "C157") (pin "1") (pinfunction "1_1") (pintype "passive"))
      (node (ref "C158") (pin "1") (pinfunction "1_1") (pintype "passive"))
      (node (ref "C159") (pin "1") (pinfunction "1_1") (pintype "passive"))
      (node (ref "C160") (pin "1") (pinfunction "1_1") (pintype "passive"))
      (node (ref "C161") (pin "1") (pinfunction "1_1") (pintype "passive"))
      (node (ref "C162") (pin "1") (pinfunction "1_1") (pintype "passive"))
      (node (ref "C163") (pin "1") (pinfunction "1_1") (pintype "passive"))
      (node (ref "C164") (pin "1") (pinfunction "1_1") (pintype "passive"))
      (node (ref "C165") (pin "1") (pinfunction "1_1") (pintype "passive"))
      (node (ref "C166") (pin "1") (pinfunction "1_1") (pintype "passive"))
      (node (ref "C167") (pin "1") (pinfunction "1_1") (pintype "passive"))
      (node (ref "C168") (pin "1") (pinfunction "1_1") (pintype "passive"))
      (node (ref "C169") (pin "1") (pinfunction "1_1") (pintype "passive"))
      (node (ref "C170") (pin "1") (pinfunction "1_1") (pintype "passive"))
      (node (ref "C171") (pin "1") (pinfunction "1_1") (pintype "passive"))
      (node (ref "C172") (pin "1") (pinfunction "1_1") (pintype "passive"))
      (node (ref "C173") (pin "1") (pinfunction "1_1") (pintype "passive"))
      (node (ref "C174") (pin "2") (pinfunction "2_2") (pintype "passive"))
      (node (ref "C175") (pin "2") (pinfunction "2_2") (pintype "passive"))
      (node (ref "C176") (pin "1") (pinfunction "1_1") (pintype "passive"))
      (node (ref "C177") (pin "1") (pinfunction "1_1") (pintype "passive"))
      (node (ref "C178") (pin "1") (pinfunction "1_1") (pintype "passive"))
      (node (ref "C179") (pin "1") (pinfunction "1_1") (pintype "passive"))
      (node (ref "C180") (pin "2") (pinfunction "2_2") (pintype "passive"))
      (node (ref "C181") (pin "2") (pinfunction "2_2") (pintype "passive"))
      (node (ref "C182") (pin "2") (pinfunction "2_2") (pintype "passive"))
      (node (ref "C183") (pin "2") (pinfunction "2_2") (pintype "passive"))
      (node (ref "C184") (pin "2") (pinfunction "2_2") (pintype "passive"))
      (node (ref "C185") (pin "2") (pinfunction "2_2") (pintype "passive"))
      (node (ref "C186") (pin "1") (pinfunction "1_1") (pintype "passive"))
      (node (ref "C187") (pin "1") (pinfunction "1_1") (pintype "passive"))
      (node (ref "C188") (pin "1") (pinfunction "1_1") (pintype "passive"))
      (node (ref "C189") (pin "1") (pinfunction "1_1") (pintype "passive"))
      (node (ref "C190") (pin "1") (pinfunction "1_1") (pintype "passive"))
      (node (ref "C191") (pin "1") (pinfunction "1_1") (pintype "passive"))
      (node (ref "C192") (pin "1") (pinfunction "1_1") (pintype "passive"))
      (node (ref "C193") (pin "2") (pinfunction "2_2") (pintype "passive"))
      (node (ref "C194") (pin "1") (pinfunction "1_1") (pintype "passive"))
      (node (ref "C195") (pin "2") (pinfunction "2_2") (pintype "passive"))
      (node (ref "C196") (pin "1") (pinfunction "1_1") (pintype "passive"))
      (node (ref "C197") (pin "1") (pinfunction "1_1") (pintype "passive"))
      (node (ref "C198") (pin "1") (pinfunction "1_1") (pintype "passive"))
      (node (ref "IC10") (pin "4") (pinfunction "GND_4") (pintype "passive"))
      (node (ref "IC10") (pin "5") (pinfunction "A2_5") (pintype "passive"))
      (node (ref "IC10") (pin "6") (pinfunction "A1_6") (pintype "passive"))
      (node (ref "IC10") (pin "7") (pinfunction "A0_7") (pintype "passive"))
      (node (ref "IC11") (pin "5") (pinfunction "GND_5") (pintype "power_in"))
      (node (ref "IC12") (pin "1") (pinfunction "E0_1") (pintype "input"))
      (node (ref "IC12") (pin "2") (pinfunction "E1_2") (pintype "input"))
      (node (ref "IC12") (pin "3") (pinfunction "E2_3") (pintype "input"))
      (node (ref "IC12") (pin "4") (pinfunction "VSS_4") (pintype "power_in"))
      (node (ref "IC12") (pin "7") (pinfunction "~{WC}_7") (pintype "input"))
      (node (ref "IC12") (pin "PAD") (pinfunction "PAD_PAD") (pintype "power_in"))
      (node (ref "IC13") (pin "2") (pinfunction "GND_2") (pintype "passive"))
      (node (ref "IC13") (pin "PAD") (pinfunction "PAD_PAD") (pintype "passive"))
      (node (ref "IC14") (pin "4") (pinfunction "SGND_4") (pintype "passive"))
      (node (ref "IC14") (pin "6") (pinfunction "PGND_6") (pintype "passive"))
      (node (ref "IC14") (pin "PAD") (pinfunction "PAD_(SGND)_PAD") (pintype "passive"))
      (node (ref "IC15") (pin "3") (pinfunction "W_3") (pintype "passive"))
      (node (ref "IC15") (pin "4") (pinfunction "GND_4") (pintype "passive"))
      (node (ref "IC15") (pin "PAD") (pinfunction "GND_PAD") (pintype "passive"))
      (node (ref "IC16") (pin "8") (pinfunction "GND_8") (pintype "passive"))
      (node (ref "IC17") (pin "3") (pinfunction "VSS_3") (pintype "power_in"))
      (node (ref "IC18") (pin "2") (pinfunction "GND_2") (pintype "passive"))
      (node (ref "IC18") (pin "PAD") (pinfunction "PAD_PAD") (pintype "passive"))
      (node (ref "IC19") (pin "4") (pinfunction "SGND_4") (pintype "passive"))
      (node (ref "IC19") (pin "6") (pinfunction "PGND_6") (pintype "passive"))
      (node (ref "IC19") (pin "PAD") (pinfunction "PAD_(SGND)_PAD") (pintype "passive"))
      (node (ref "IC9") (pin "1") (pinfunction "GND_1") (pintype "passive"))
      (node (ref "IC9") (pin "11") (pinfunction "GND_11") (pintype "passive"))
      (node (ref "IC9") (pin "12") (pinfunction "GND_12") (pintype "passive"))
      (node (ref "IC9") (pin "16") (pinfunction "GND_16") (pintype "passive"))
      (node (ref "IC9") (pin "19") (pinfunction "GND_19") (pintype "passive"))
      (node (ref "IC9") (pin "22") (pinfunction "SEL_22") (pintype "passive"))
      (node (ref "IC9") (pin "25") (pinfunction "GND_25") (pintype "passive"))
      (node (ref "IC9") (pin "7") (pinfunction "GND_7") (pintype "passive"))
      (node (ref "J7") (pin "2") (pinfunction "Y_2") (pintype "passive"))
      (node (ref "J8") (pin "2") (pinfunction "Y_2") (pintype "passive"))
      (node (ref "R100") (pin "1") (pinfunction "1_1") (pintype "passive"))
      (node (ref "R67") (pin "1") (pinfunction "1_1") (pintype "passive"))
      (node (ref "R73") (pin "2") (pinfunction "2_2") (pintype "passive"))
      (node (ref "R80") (pin "2") (pinfunction "2_2") (pintype "passive"))
      (node (ref "R82") (pin "1") (pinfunction "1_1") (pintype "passive"))
      (node (ref "R83") (pin "2") (pinfunction "2_2") (pintype "passive"))
      (node (ref "R89") (pin "2") (pinfunction "2_2") (pintype "passive"))
      (node (ref "R91") (pin "1") (pinfunction "1_1") (pintype "passive"))
      (node (ref "VT4") (pin "S") (pinfunction "S_S") (pintype "passive"))
      (node (ref "XO1") (pin "4") (pinfunction "GND_4") (pintype "passive"))
    )
    (net (code "34") (name "Net-(C154-Pad1)") (class "Default")
      (node (ref "C154") (pin "1") (pinfunction "1_1") (pintype "passive"))
      (node (ref "C155") (pin "2") (pinfunction "2_2") (pintype "passive"))
      (node (ref "R67") (pin "2") (pinfunction "2_2") (pintype "passive"))
    )
    (net (code "35") (name "Net-(C154-Pad2)") (class "Default")
      (node (ref "C154") (pin "2") (pinfunction "2_2") (pintype "passive"))
      (node (ref "R63") (pin "2") (pinfunction "2_2") (pintype "passive"))
      (node (ref "R66") (pin "2") (pinfunction "2_2") (pintype "passive"))
    )
    (net (code "36") (name "Net-(C159-Pad2)") (class "Default")
      (node (ref "C159") (pin "2") (pinfunction "2_2") (pintype "passive"))
      (node (ref "FR38") (pin "1") (pinfunction "1_1") (pintype "passive"))
      (node (ref "R64") (pin "1") (pinfunction "1_1") (pintype "passive"))
    )
    (net (code "37") (name "Net-(C195-Pad1)") (class "Default")
      (node (ref "C195") (pin "1") (pinfunction "1_1") (pintype "passive"))
      (node (ref "J9") (pin "2") (pinfunction "2_2") (pintype "passive"))
      (node (ref "R94") (pin "2") (pinfunction "2_2") (pintype "passive"))
      (node (ref "R96") (pin "2") (pinfunction "2_2") (pintype "passive"))
    )
    (net (code "38") (name "Net-(IC9-CLKin)") (class "Default")
      (node (ref "C155") (pin "1") (pinfunction "1_1") (pintype "passive"))
      (node (ref "IC9") (pin "21") (pinfunction "CLKin_21") (pintype "passive"))
    )
    (net (code "39") (name "Net-(IC9-CLKin*)") (class "Default")
      (node (ref "C162") (pin "2") (pinfunction "2_2") (pintype "passive"))
      (node (ref "IC9") (pin "20") (pinfunction "CLKin*_20") (pintype "passive"))
    )
    (net (code "40") (name "Net-(IC9-CLKout0)") (class "Default")
      (node (ref "IC9") (pin "3") (pinfunction "CLKout0_3") (pintype "passive"))
      (node (ref "R65") (pin "2") (pinfunction "2_2") (pintype "passive"))
    )
    (net (code "41") (name "Net-(IC9-CLKout1)") (class "Default")
      (node (ref "IC9") (pin "5") (pinfunction "CLKout1_5") (pintype "passive"))
      (node (ref "R69") (pin "2") (pinfunction "2_2") (pintype "passive"))
    )
    (net (code "42") (name "Net-(IC9-OE)") (class "Default")
      (node (ref "IC9") (pin "24") (pinfunction "OE_24") (pintype "passive"))
      (node (ref "R61") (pin "1") (pinfunction "1_1") (pintype "passive"))
    )
    (net (code "43") (name "Net-(IC11-VDD)") (class "Default")
      (node (ref "C175") (pin "1") (pinfunction "1_1") (pintype "passive"))
      (node (ref "FR41") (pin "2") (pinfunction "2_2") (pintype "passive"))
      (node (ref "IC11") (pin "4") (pinfunction "VDD_4") (pintype "power_in"))
    )
    (net (code "44") (name "Net-(IC11-VOUT)") (class "Default")
      (node (ref "IC11") (pin "6") (pinfunction "VOUT_6") (pintype "tri_state"))
      (node (ref "R72") (pin "2") (pinfunction "2_2") (pintype "passive"))
    )
    (net (code "45") (name "Net-(IC13-ADJ)") (class "Default")
      (node (ref "IC13") (pin "5") (pinfunction "ADJ_5") (pintype "input"))
      (node (ref "R74") (pin "1") (pinfunction "1_1") (pintype "passive"))
      (node (ref "R80") (pin "1") (pinfunction "1_1") (pintype "passive"))
    )
    (net (code "46") (name "Net-(IC14-VCON)") (class "Default")
      (node (ref "C182") (pin "1") (pinfunction "1_1") (pintype "passive"))
      (node (ref "IC14") (pin "2") (pinfunction "VCON_2") (pintype "input"))
      (node (ref "R79") (pin "1") (pinfunction "1_1") (pintype "passive"))
      (node (ref "R82") (pin "2") (pinfunction "2_2") (pintype "passive"))
    )
    (net (code "47") (name "Net-(IC14-VREF)") (class "Default")
      (node (ref "IC14") (pin "8") (pinfunction "VREF_8") (pintype "output"))
      (node (ref "R79") (pin "2") (pinfunction "2_2") (pintype "passive"))
    )
    (net (code "48") (name "Net-(IC16-Vdd)") (class "Default")
      (node (ref "C180") (pin "1") (pinfunction "1_1") (pintype "passive"))
      (node (ref "FR42") (pin "2") (pinfunction "2_2") (pintype "passive"))
      (node (ref "IC16") (pin "1") (pinfunction "Vdd_1") (pintype "power_in"))
      (node (ref "R76") (pin "2") (pinfunction "2_2") (pintype "passive"))
    )
    (net (code "49") (name "Net-(IC17-IN)") (class "Default")
      (node (ref "C185") (pin "1") (pinfunction "1_1") (pintype "passive"))
      (node (ref "C187") (pin "2") (pinfunction "2_2") (pintype "passive"))
      (node (ref "FR43") (pin "2") (pinfunction "2_2") (pintype "passive"))
      (node (ref "IC17") (pin "1") (pinfunction "IN_1") (pintype "power_in"))
    )
    (net (code "50") (name "Net-(IC18-ADJ)") (class "Default")
      (node (ref "IC18") (pin "5") (pinfunction "ADJ_5") (pintype "input"))
      (node (ref "R84") (pin "1") (pinfunction "1_1") (pintype "passive"))
      (node (ref "R89") (pin "1") (pinfunction "1_1") (pintype "passive"))
    )
    (net (code "51") (name "Net-(IC18-PG)") (class "Default")
      (node (ref "C192") (pin "2") (pinfunction "2_2") (pintype "passive"))
      (node (ref "IC18") (pin "3") (pinfunction "PG_3") (pintype "output"))
    )
    (net (code "52") (name "Net-(IC19-VCON)") (class "Default")
      (node (ref "C193") (pin "1") (pinfunction "1_1") (pintype "passive"))
      (node (ref "IC19") (pin "2") (pinfunction "VCON_2") (pintype "input"))
      (node (ref "R88") (pin "1") (pinfunction "1_1") (pintype "passive"))
      (node (ref "R91") (pin "2") (pinfunction "2_2") (pintype "passive"))
    )
    (net (code "53") (name "Net-(IC19-VREF)") (class "Default")
      (node (ref "IC19") (pin "8") (pinfunction "VREF_8") (pintype "output"))
      (node (ref "R88") (pin "2") (pinfunction "2_2") (pintype "passive"))
    )
    (net (code "54") (name "Net-(J9-Pad1)") (class "Default")
      (node (ref "J9") (pin "1") (pinfunction "1_1") (pintype "passive"))
      (node (ref "R100") (pin "2") (pinfunction "2_2") (pintype "passive"))
      (node (ref "VT4") (pin "D") (pinfunction "D_D") (pintype "passive"))
    )
    (net (code "55") (name "Net-(LED1-Pad3)") (class "Default")
      (node (ref "LED1") (pin "3") (pinfunction "3_3") (pintype "power_in"))
      (node (ref "R85") (pin "1") (pinfunction "1_1") (pintype "passive"))
    )
    (net (code "56") (name "Net-(LED1-Pad4)") (class "Default")
      (node (ref "LED1") (pin "4") (pinfunction "4_4") (pintype "power_in"))
      (node (ref "R87") (pin "1") (pinfunction "1_1") (pintype "passive"))
    )
    (net (code "57") (name "Net-(LED2-Pad3)") (class "Default")
      (node (ref "LED2") (pin "3") (pinfunction "3_3") (pintype "power_in"))
      (node (ref "R92") (pin "1") (pinfunction "1_1") (pintype "passive"))
    )
    (net (code "58") (name "Net-(LED2-Pad4)") (class "Default")
      (node (ref "LED2") (pin "4") (pinfunction "4_4") (pintype "power_in"))
      (node (ref "R95") (pin "1") (pinfunction "1_1") (pintype "passive"))
    )
    (net (code "59") (name "Net-(LED3-Pad3)") (class "Default")
      (node (ref "LED3") (pin "3") (pinfunction "3_3") (pintype "power_in"))
      (node (ref "R97") (pin "1") (pinfunction "1_1") (pintype "passive"))
    )
    (net (code "60") (name "Net-(LED3-Pad4)") (class "Default")
      (node (ref "LED3") (pin "4") (pinfunction "4_4") (pintype "power_in"))
      (node (ref "R99") (pin "1") (pinfunction "1_1") (pintype "passive"))
    )
    (net (code "61") (name "Net-(XO1-RF_OUT)") (class "Default")
      (node (ref "R63") (pin "1") (pinfunction "1_1") (pintype "passive"))
      (node (ref "XO1") (pin "6") (pinfunction "RF_OUT_6") (pintype "output"))
    )
    (net (code "62") (name "Net-(XO1-VC_FILTER)") (class "Default")
      (node (ref "C157") (pin "2") (pinfunction "2_2") (pintype "passive"))
      (node (ref "XO1") (pin "7") (pinfunction "VC_FILTER_7") (pintype "input"))
    )
    (net (code "63") (name "VCC1P1") (class "Default")
      (node (ref "C179") (pin "2") (pinfunction "2_2") (pintype "passive"))
      (node (ref "IC13") (pin "4") (pinfunction "Vout_4") (pintype "output"))
      (node (ref "R74") (pin "2") (pinfunction "2_2") (pintype "passive"))
    )
    (net (code "64") (name "VCC1P8") (class "Default")
      (node (ref "C177") (pin "2") (pinfunction "2_2") (pintype "passive"))
      (node (ref "C178") (pin "2") (pinfunction "2_2") (pintype "passive"))
      (node (ref "FR40") (pin "1") (pinfunction "1_1") (pintype "passive"))
      (node (ref "IC13") (pin "1") (pinfunction "EN_1") (pintype "input"))
      (node (ref "IC13") (pin "6") (pinfunction "Vin_6") (pintype "input"))
      (node (ref "IC14") (pin "3") (pinfunction "FB_3") (pintype "input"))
      (node (ref "IC14") (pin "5") (pinfunction "VOUT_5") (pintype "output"))
      (node (ref "R62") (pin "2") (pinfunction "2_2") (pintype "passive"))
      (node (ref "R93") (pin "2") (pinfunction "2_2") (pintype "passive"))
    )
    (net (code "65") (name "VCC2P5") (class "Default")
      (node (ref "C191") (pin "2") (pinfunction "2_2") (pintype "passive"))
      (node (ref "IC18") (pin "4") (pinfunction "Vout_4") (pintype "output"))
      (node (ref "R81") (pin "2") (pinfunction "2_2") (pintype "passive"))
      (node (ref "R84") (pin "2") (pinfunction "2_2") (pintype "passive"))
      (node (ref "R98") (pin "1") (pinfunction "1_1") (pintype "passive"))
    )
    (net (code "66") (name "VCC2P5_VREF") (class "Default")
      (node (ref "C186") (pin "2") (pinfunction "2_2") (pintype "passive"))
      (node (ref "IC17") (pin "2") (pinfunction "OUT_2") (pintype "power_in"))
      (node (ref "R78") (pin "1") (pinfunction "1_1") (pintype "passive"))
    )
    (net (code "67") (name "VCC3P3") (class "Default")
      (node (ref "C156") (pin "1") (pinfunction "1_1") (pintype "passive"))
      (node (ref "C174") (pin "1") (pinfunction "1_1") (pintype "passive"))
      (node (ref "C181") (pin "1") (pinfunction "1_1") (pintype "passive"))
      (node (ref "C189") (pin "2") (pinfunction "2_2") (pintype "passive"))
      (node (ref "C190") (pin "2") (pinfunction "2_2") (pintype "passive"))
      (node (ref "FR44") (pin "1") (pinfunction "1_1") (pintype "passive"))
      (node (ref "IC10") (pin "8") (pinfunction "VCC_8") (pintype "passive"))
      (node (ref "IC12") (pin "8") (pinfunction "VCC_8") (pintype "power_in"))
      (node (ref "IC15") (pin "7") (pinfunction "HOLD_7") (pintype "passive"))
      (node (ref "IC15") (pin "8") (pinfunction "VCC_8") (pintype "passive"))
      (node (ref "IC18") (pin "1") (pinfunction "EN_1") (pintype "input"))
      (node (ref "IC18") (pin "6") (pinfunction "Vin_6") (pintype "input"))
      (node (ref "IC19") (pin "3") (pinfunction "FB_3") (pintype "input"))
      (node (ref "IC19") (pin "5") (pinfunction "VOUT_5") (pintype "output"))
      (node (ref "LED1") (pin "1") (pinfunction "1_1") (pintype "power_in"))
      (node (ref "LED1") (pin "2") (pinfunction "2_2") (pintype "power_in"))
      (node (ref "LED2") (pin "1") (pinfunction "1_1") (pintype "power_in"))
      (node (ref "LED2") (pin "2") (pinfunction "2_2") (pintype "power_in"))
      (node (ref "LED3") (pin "1") (pinfunction "1_1") (pintype "power_in"))
      (node (ref "LED3") (pin "2") (pinfunction "2_2") (pintype "power_in"))
      (node (ref "R101") (pin "1") (pinfunction "1_1") (pintype "passive"))
      (node (ref "R68") (pin "1") (pinfunction "1_1") (pintype "passive"))
      (node (ref "R70") (pin "1") (pinfunction "1_1") (pintype "passive"))
      (node (ref "R75") (pin "2") (pinfunction "2_2") (pintype "passive"))
      (node (ref "R77") (pin "2") (pinfunction "2_2") (pintype "passive"))
      (node (ref "R96") (pin "1") (pinfunction "1_1") (pintype "passive"))
    )
    (net (code "68") (name "VCC3P3_CLK") (class "Default")
      (node (ref "C196") (pin "2") (pinfunction "2_2") (pintype "passive"))
      (node (ref "FR39") (pin "1") (pinfunction "1_1") (pintype "passive"))
      (node (ref "FR41") (pin "1") (pinfunction "1_1") (pintype "passive"))
      (node (ref "FR42") (pin "1") (pinfunction "1_1") (pintype "passive"))
      (node (ref "FR43") (pin "1") (pinfunction "1_1") (pintype "passive"))
      (node (ref "FR44") (pin "2") (pinfunction "2_2") (pintype "passive"))
      (node (ref "R64") (pin "2") (pinfunction "2_2") (pintype "passive"))
    )
    (net (code "69") (name "VCC3P3_XO") (class "Default")
      (node (ref "C161") (pin "2") (pinfunction "2_2") (pintype "passive"))
      (node (ref "FR38") (pin "2") (pinfunction "2_2") (pintype "passive"))
      (node (ref "R71") (pin "2") (pinfunction "2_2") (pintype "passive"))
      (node (ref "XO1") (pin "9") (pinfunction "VCC_9") (pintype "power_in"))
    )
    (net (code "70") (name "VCC5P0") (class "Default")
      (node (ref "C176") (pin "2") (pinfunction "2_2") (pintype "passive"))
      (node (ref "C188") (pin "2") (pinfunction "2_2") (pintype "passive"))
      (node (ref "IC14") (pin "1") (pinfunction "EN_1") (pintype "input"))
      (node (ref "IC14") (pin "7") (pinfunction "VIN_7") (pintype "input"))
      (node (ref "IC19") (pin "7") (pinfunction "VIN_7") (pintype "input"))
      (node (ref "R86") (pin "2") (pinfunction "2_2") (pintype "passive"))
      (node (ref "R94") (pin "1") (pinfunction "1_1") (pintype "passive"))
    )
    (net (code "71") (name "VDIO_LMS") (class "Default")
      (node (ref "C198") (pin "2") (pinfunction "2_2") (pintype "passive"))
      (node (ref "FR45") (pin "2") (pinfunction "2_2") (pintype "passive"))
    )
    (net (code "72") (name "VDIO_LMS_FPGA") (class "Default")
      (node (ref "C197") (pin "2") (pinfunction "2_2") (pintype "passive"))
      (node (ref "FR45") (pin "1") (pinfunction "1_1") (pintype "passive"))
      (node (ref "R101") (pin "2") (pinfunction "2_2") (pintype "passive"))
      (node (ref "R98") (pin "2") (pinfunction "2_2") (pintype "passive"))
    )
    (net (code "73") (name "unconnected-(IC9-CLKout3-Pad15)") (class "Default")
      (node (ref "IC9") (pin "15") (pinfunction "CLKout3_15") (pintype "passive+no_connect"))
    )
    (net (code "74") (name "unconnected-(IC9-OSCin-Pad9)") (class "Default")
      (node (ref "IC9") (pin "9") (pinfunction "OSCin_9") (pintype "passive+no_connect"))
    )
    (net (code "75") (name "unconnected-(IC9-OSCout-Pad10)") (class "Default")
      (node (ref "IC9") (pin "10") (pinfunction "OSCout_10") (pintype "passive+no_connect"))
    )
    (net (code "76") (name "unconnected-(XO1-NC-Pad2)") (class "Default")
      (node (ref "XO1") (pin "2") (pinfunction "NC_2") (pintype "passive+no_connect"))
    )
    (net (code "77") (name "unconnected-(XO1-NC-Pad3)") (class "Default")
      (node (ref "XO1") (pin "3") (pinfunction "NC_3") (pintype "passive+no_connect"))
    )
    (net (code "78") (name "unconnected-(XO1-NC-Pad5)") (class "Default")
      (node (ref "XO1") (pin "5") (pinfunction "NC_5") (pintype "passive+no_connect"))
    )
    (net (code "79") (name "unconnected-(XO1-NC-Pad8)") (class "Default")
      (node (ref "XO1") (pin "8") (pinfunction "NC_8") (pintype "passive+no_connect"))
    )
    (net (code "80") (name "unconnected-(XO1-NC-Pad10)") (class "Default")
      (node (ref "XO1") (pin "10") (pinfunction "NC_10") (pintype "passive+no_connect"))
    )
  )
)
